# 1-Schematic_Delta.net
KiCad netlist of a schematic drawn in EasyEDA
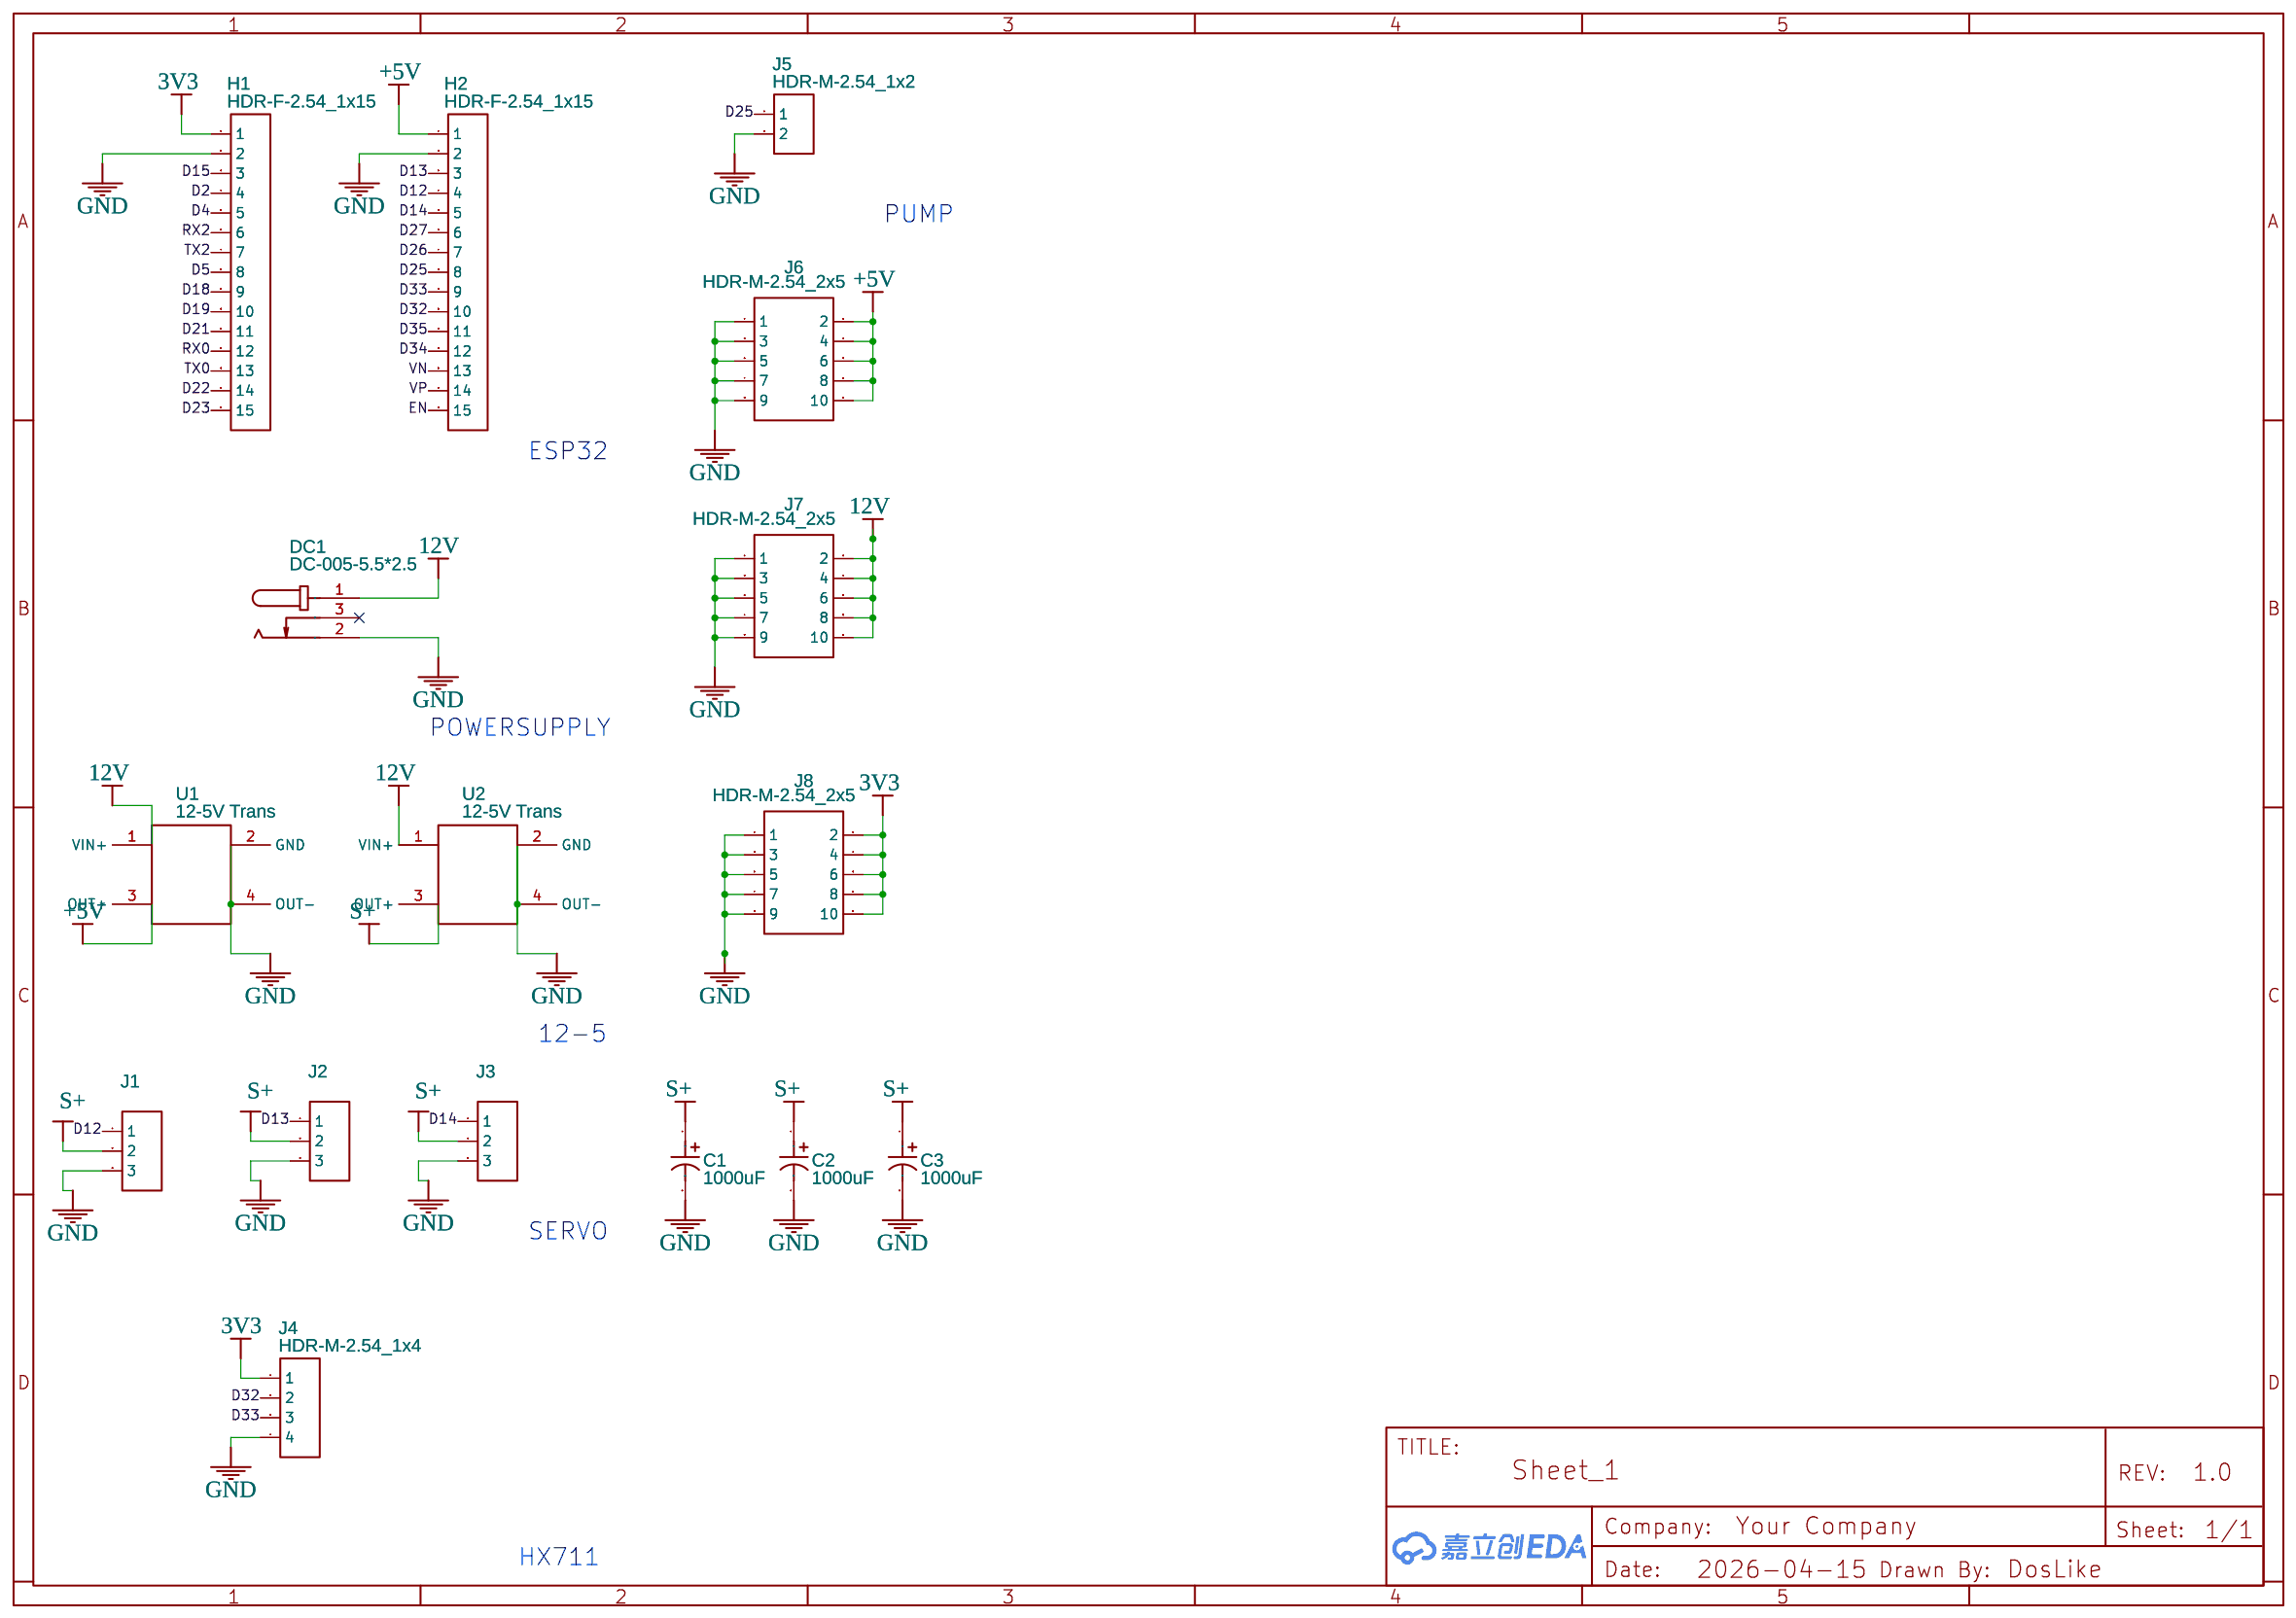
[diagram p0: schematic sheet]

(export (version "E")
  (design (tool "Eeschema 10.0.6"))
  (components
    (comp (ref "C1")
      (value "1000uF")
      (fields
        (field (name "Manufacturer Part") "RYHS16V1000UF6*15")
        (field (name "Manufacturer") "HONOR(荣誉)")
      )
      (libsource (lib "") (part "RYHS16V1000UF6*15"))
    )
    (comp (ref "C2")
      (value "1000uF")
      (fields
        (field (name "Manufacturer Part") "RYHS16V1000UF6*15")
        (field (name "Manufacturer") "HONOR(荣誉)")
      )
      (libsource (lib "") (part "RYHS16V1000UF6*15"))
    )
    (comp (ref "C3")
      (value "1000uF")
      (fields
        (field (name "Manufacturer Part") "RYHS16V1000UF6*15")
        (field (name "Manufacturer") "HONOR(荣誉)")
      )
      (libsource (lib "") (part "RYHS16V1000UF6*15"))
    )
    (comp (ref "DC1") (value "DC-005-5.5*2.5") (libsource (lib "") (part "DC-005-5.5*2.5")))
    (comp (ref "H1") (value "HDR-F-2.54_1x15") (libsource (lib "") (part "HDR-F-2.54_1x15")))
    (comp (ref "H2") (value "HDR-F-2.54_1x15") (libsource (lib "") (part "HDR-F-2.54_1x15")))
    (comp (ref "J1") (value "3") (libsource (lib "") (part "HDR-M-2.54_1x3")))
    (comp (ref "J2") (value "HDR-M-2.54_1x3") (libsource (lib "") (part "HDR-M-2.54_1x3")))
    (comp (ref "J3") (value "HDR-M-2.54_1x3") (libsource (lib "") (part "HDR-M-2.54_1x3")))
    (comp (ref "J4") (value "HDR-M-2.54_1x4") (libsource (lib "") (part "HDR-M-2.54_1x4")))
    (comp (ref "J5") (value "HDR-M-2.54_1x2") (libsource (lib "") (part "HDR-M-2.54_1x2")))
    (comp (ref "J6") (value "HDR-M-2.54_2x5") (libsource (lib "") (part "HDR-M-2.54_2x5")))
    (comp (ref "J7") (value "HDR-M-2.54_2x5") (libsource (lib "") (part "HDR-M-2.54_2x5")))
    (comp (ref "J8") (value "HDR-M-2.54_2x5") (libsource (lib "") (part "HDR-M-2.54_2x5")))
    (comp (ref "U1") (value "12-5V Trans") (libsource (lib "") (part "12-5V Trans")))
    (comp (ref "U2") (value "12-5V Trans") (libsource (lib "") (part "12-5V Trans")))
  )
  (nets
    (net (code "1") (name "+5V") (class "Default")
      (node (ref "H2") (pin "1") (pinfunction "1_1") (pintype "unspecified"))
      (node (ref "J6") (pin "10") (pinfunction "10_10") (pintype "unspecified"))
      (node (ref "J6") (pin "2") (pinfunction "2_2") (pintype "unspecified"))
      (node (ref "J6") (pin "4") (pinfunction "4_4") (pintype "unspecified"))
      (node (ref "J6") (pin "6") (pinfunction "6_6") (pintype "unspecified"))
      (node (ref "J6") (pin "8") (pinfunction "8_8") (pintype "unspecified"))
      (node (ref "U1") (pin "3") (pinfunction "OUT+_3") (pintype "unspecified"))
    )
    (net (code "2") (name "/D2") (class "Default")
      (node (ref "H1") (pin "4") (pinfunction "4_4") (pintype "unspecified"))
    )
    (net (code "3") (name "/D4") (class "Default")
      (node (ref "H1") (pin "5") (pinfunction "5_5") (pintype "unspecified"))
    )
    (net (code "4") (name "/D5") (class "Default")
      (node (ref "H1") (pin "8") (pinfunction "8_8") (pintype "unspecified"))
    )
    (net (code "5") (name "/D12") (class "Default")
      (node (ref "H2") (pin "4") (pinfunction "4_4") (pintype "unspecified"))
      (node (ref "J1") (pin "1") (pinfunction "1_1") (pintype "input"))
    )
    (net (code "6") (name "/D13") (class "Default")
      (node (ref "H2") (pin "3") (pinfunction "3_3") (pintype "unspecified"))
      (node (ref "J2") (pin "1") (pinfunction "1_1") (pintype "input"))
    )
    (net (code "7") (name "/D14") (class "Default")
      (node (ref "H2") (pin "5") (pinfunction "5_5") (pintype "unspecified"))
      (node (ref "J3") (pin "1") (pinfunction "1_1") (pintype "input"))
    )
    (net (code "8") (name "/D15") (class "Default")
      (node (ref "H1") (pin "3") (pinfunction "3_3") (pintype "unspecified"))
    )
    (net (code "9") (name "/D18") (class "Default")
      (node (ref "H1") (pin "9") (pinfunction "9_9") (pintype "unspecified"))
    )
    (net (code "10") (name "/D19") (class "Default")
      (node (ref "H1") (pin "10") (pinfunction "10_10") (pintype "unspecified"))
    )
    (net (code "11") (name "/D21") (class "Default")
      (node (ref "H1") (pin "11") (pinfunction "11_11") (pintype "unspecified"))
    )
    (net (code "12") (name "/D22") (class "Default")
      (node (ref "H1") (pin "14") (pinfunction "14_14") (pintype "unspecified"))
    )
    (net (code "13") (name "/D23") (class "Default")
      (node (ref "H1") (pin "15") (pinfunction "15_15") (pintype "unspecified"))
    )
    (net (code "14") (name "/D25") (class "Default")
      (node (ref "H2") (pin "8") (pinfunction "8_8") (pintype "unspecified"))
      (node (ref "J5") (pin "1") (pinfunction "1_1") (pintype "unspecified"))
    )
    (net (code "15") (name "/D26") (class "Default")
      (node (ref "H2") (pin "7") (pinfunction "7_7") (pintype "unspecified"))
    )
    (net (code "16") (name "/D27") (class "Default")
      (node (ref "H2") (pin "6") (pinfunction "6_6") (pintype "unspecified"))
    )
    (net (code "17") (name "/D32") (class "Default")
      (node (ref "H2") (pin "10") (pinfunction "10_10") (pintype "unspecified"))
      (node (ref "J4") (pin "2") (pinfunction "2_2") (pintype "unspecified"))
    )
    (net (code "18") (name "/D33") (class "Default")
      (node (ref "H2") (pin "9") (pinfunction "9_9") (pintype "unspecified"))
      (node (ref "J4") (pin "3") (pinfunction "3_3") (pintype "unspecified"))
    )
    (net (code "19") (name "/D34") (class "Default")
      (node (ref "H2") (pin "12") (pinfunction "12_12") (pintype "unspecified"))
    )
    (net (code "20") (name "/D35") (class "Default")
      (node (ref "H2") (pin "11") (pinfunction "11_11") (pintype "unspecified"))
    )
    (net (code "21") (name "/EN") (class "Default")
      (node (ref "H2") (pin "15") (pinfunction "15_15") (pintype "unspecified"))
    )
    (net (code "22") (name "/RX0") (class "Default")
      (node (ref "H1") (pin "12") (pinfunction "12_12") (pintype "unspecified"))
    )
    (net (code "23") (name "/RX2") (class "Default")
      (node (ref "H1") (pin "6") (pinfunction "6_6") (pintype "unspecified"))
    )
    (net (code "24") (name "/TX0") (class "Default")
      (node (ref "H1") (pin "13") (pinfunction "13_13") (pintype "unspecified"))
    )
    (net (code "25") (name "/TX2") (class "Default")
      (node (ref "H1") (pin "7") (pinfunction "7_7") (pintype "unspecified"))
    )
    (net (code "26") (name "/VN") (class "Default")
      (node (ref "H2") (pin "13") (pinfunction "13_13") (pintype "unspecified"))
    )
    (net (code "27") (name "/VP") (class "Default")
      (node (ref "H2") (pin "14") (pinfunction "14_14") (pintype "unspecified"))
    )
    (net (code "28") (name "3V3") (class "Default")
      (node (ref "H1") (pin "1") (pinfunction "1_1") (pintype "unspecified"))
      (node (ref "J4") (pin "1") (pinfunction "1_1") (pintype "unspecified"))
      (node (ref "J8") (pin "10") (pinfunction "10_10") (pintype "unspecified"))
      (node (ref "J8") (pin "2") (pinfunction "2_2") (pintype "unspecified"))
      (node (ref "J8") (pin "4") (pinfunction "4_4") (pintype "unspecified"))
      (node (ref "J8") (pin "6") (pinfunction "6_6") (pintype "unspecified"))
      (node (ref "J8") (pin "8") (pinfunction "8_8") (pintype "unspecified"))
    )
    (net (code "29") (name "12V") (class "Default")
      (node (ref "DC1") (pin "1") (pinfunction "1_1") (pintype "unspecified"))
      (node (ref "J7") (pin "10") (pinfunction "10_10") (pintype "unspecified"))
      (node (ref "J7") (pin "2") (pinfunction "2_2") (pintype "unspecified"))
      (node (ref "J7") (pin "4") (pinfunction "4_4") (pintype "unspecified"))
      (node (ref "J7") (pin "6") (pinfunction "6_6") (pintype "unspecified"))
      (node (ref "J7") (pin "8") (pinfunction "8_8") (pintype "unspecified"))
      (node (ref "U1") (pin "1") (pinfunction "VIN+_1") (pintype "unspecified"))
      (node (ref "U2") (pin "1") (pinfunction "VIN+_1") (pintype "unspecified"))
    )
    (net (code "30") (name "GND") (class "Default")
      (node (ref "C1") (pin "2") (pinfunction "2_2") (pintype "input"))
      (node (ref "C2") (pin "2") (pinfunction "2_2") (pintype "input"))
      (node (ref "C3") (pin "2") (pinfunction "2_2") (pintype "input"))
      (node (ref "DC1") (pin "2") (pinfunction "2_2") (pintype "unspecified"))
      (node (ref "H1") (pin "2") (pinfunction "2_2") (pintype "unspecified"))
      (node (ref "H2") (pin "2") (pinfunction "2_2") (pintype "unspecified"))
      (node (ref "J1") (pin "3") (pinfunction "3_3") (pintype "input"))
      (node (ref "J2") (pin "3") (pinfunction "3_3") (pintype "input"))
      (node (ref "J3") (pin "3") (pinfunction "3_3") (pintype "input"))
      (node (ref "J4") (pin "4") (pinfunction "4_4") (pintype "unspecified"))
      (node (ref "J5") (pin "2") (pinfunction "2_2") (pintype "unspecified"))
      (node (ref "J6") (pin "1") (pinfunction "1_1") (pintype "unspecified"))
      (node (ref "J6") (pin "3") (pinfunction "3_3") (pintype "unspecified"))
      (node (ref "J6") (pin "5") (pinfunction "5_5") (pintype "unspecified"))
      (node (ref "J6") (pin "7") (pinfunction "7_7") (pintype "unspecified"))
      (node (ref "J6") (pin "9") (pinfunction "9_9") (pintype "unspecified"))
      (node (ref "J7") (pin "1") (pinfunction "1_1") (pintype "unspecified"))
      (node (ref "J7") (pin "3") (pinfunction "3_3") (pintype "unspecified"))
      (node (ref "J7") (pin "5") (pinfunction "5_5") (pintype "unspecified"))
      (node (ref "J7") (pin "7") (pinfunction "7_7") (pintype "unspecified"))
      (node (ref "J7") (pin "9") (pinfunction "9_9") (pintype "unspecified"))
      (node (ref "J8") (pin "1") (pinfunction "1_1") (pintype "unspecified"))
      (node (ref "J8") (pin "3") (pinfunction "3_3") (pintype "unspecified"))
      (node (ref "J8") (pin "5") (pinfunction "5_5") (pintype "unspecified"))
      (node (ref "J8") (pin "7") (pinfunction "7_7") (pintype "unspecified"))
      (node (ref "J8") (pin "9") (pinfunction "9_9") (pintype "unspecified"))
      (node (ref "U1") (pin "2") (pinfunction "GND_2") (pintype "unspecified"))
      (node (ref "U1") (pin "4") (pinfunction "OUT-_4") (pintype "unspecified"))
      (node (ref "U2") (pin "2") (pinfunction "GND_2") (pintype "unspecified"))
      (node (ref "U2") (pin "4") (pinfunction "OUT-_4") (pintype "unspecified"))
    )
    (net (code "31") (name "S+") (class "Default")
      (node (ref "C1") (pin "1") (pinfunction "1_1") (pintype "input"))
      (node (ref "C2") (pin "1") (pinfunction "1_1") (pintype "input"))
      (node (ref "C3") (pin "1") (pinfunction "1_1") (pintype "input"))
      (node (ref "J1") (pin "2") (pinfunction "2_2") (pintype "input"))
      (node (ref "J2") (pin "2") (pinfunction "2_2") (pintype "input"))
      (node (ref "J3") (pin "2") (pinfunction "2_2") (pintype "input"))
      (node (ref "U2") (pin "3") (pinfunction "OUT+_3") (pintype "unspecified"))
    )
    (net (code "32") (name "unconnected-(DC1-Pad3)") (class "Default")
      (node (ref "DC1") (pin "3") (pinfunction "3_3") (pintype "unspecified+no_connect"))
    )
  )
)
